# VLT_1_0.net
KiCad netlist of a schematic drawn in EAGLE
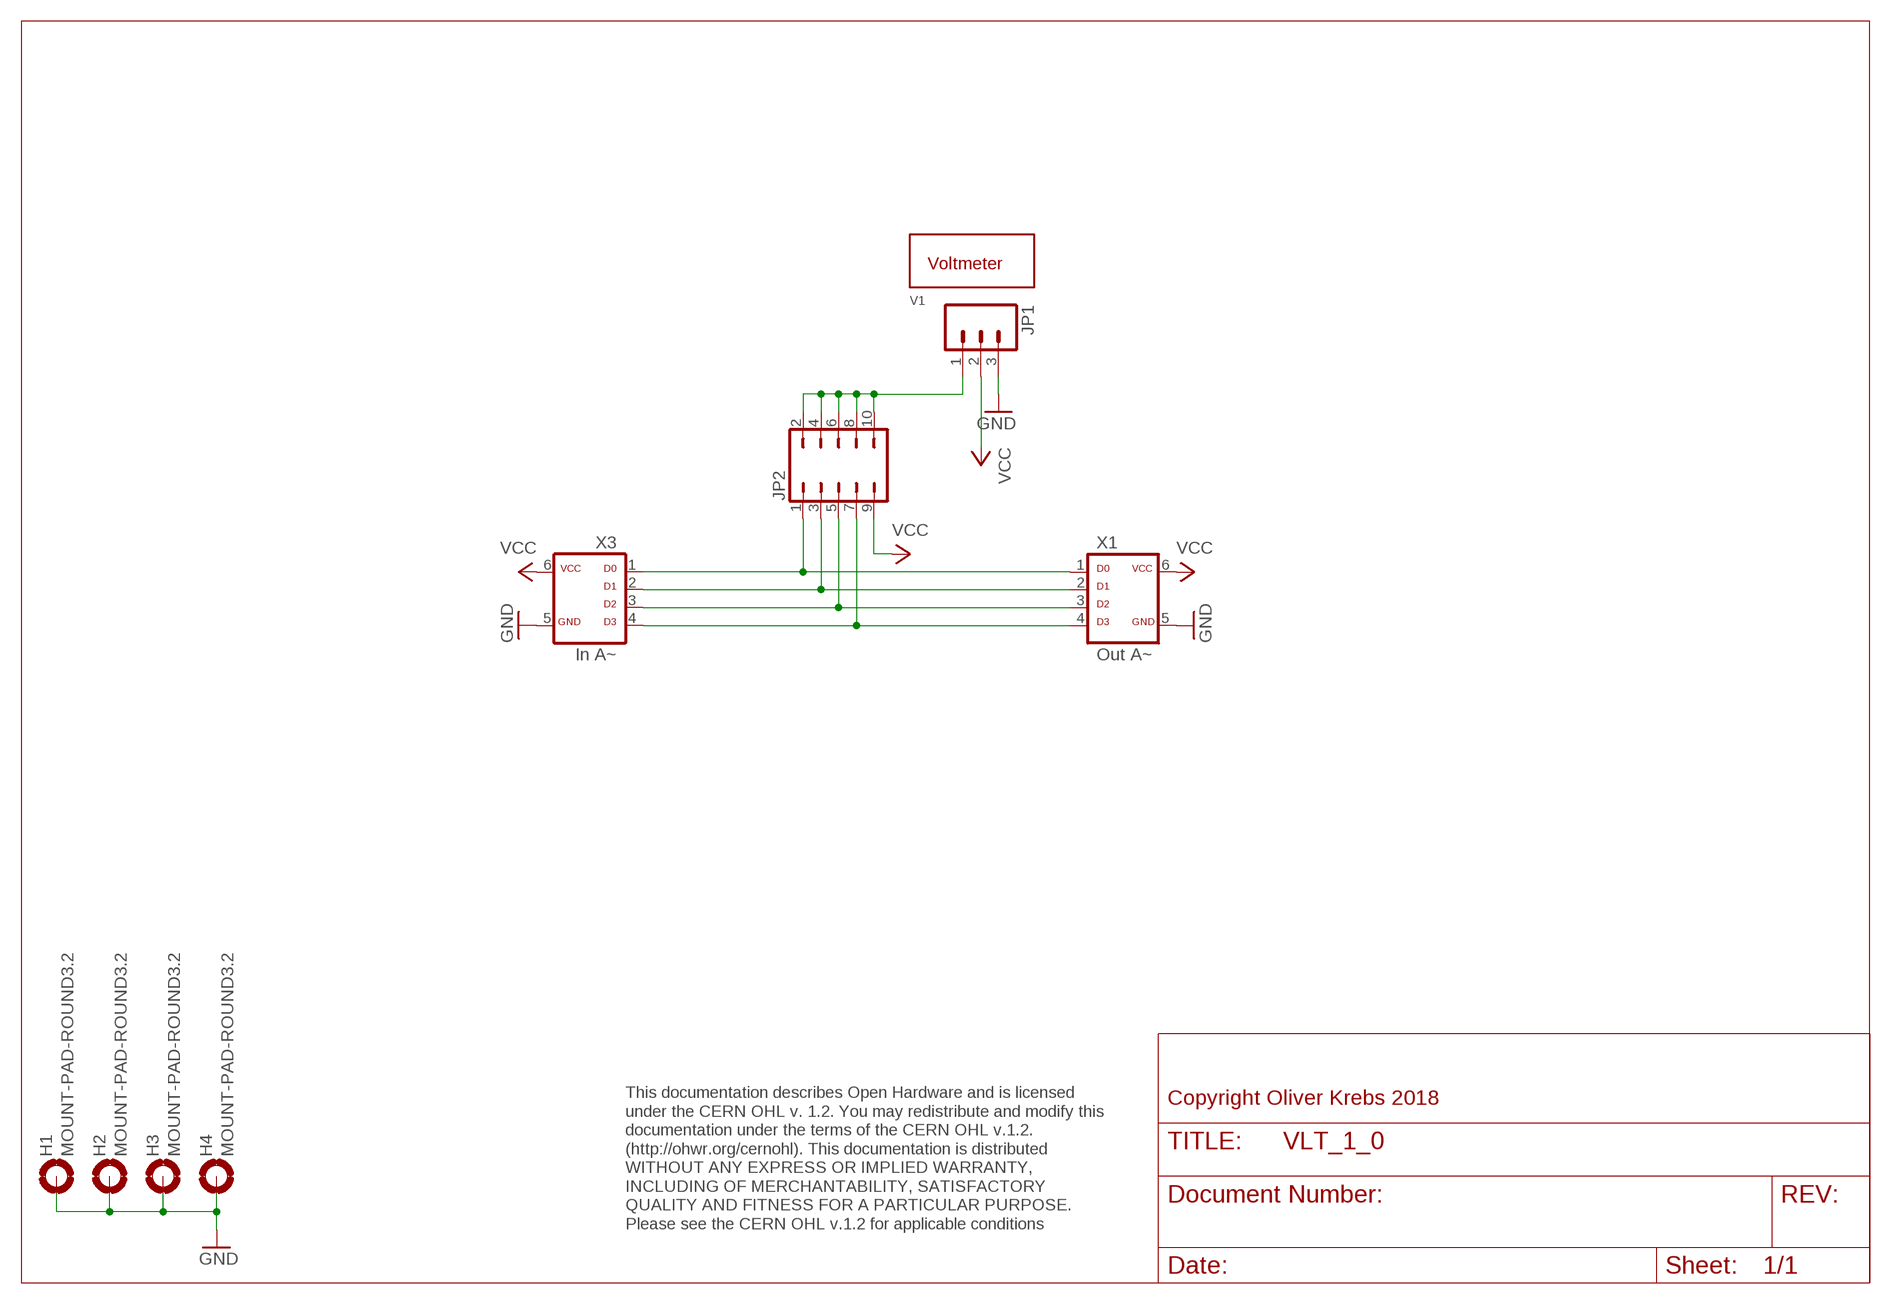
[diagram p0: schematic, sheet 1]

(export (version "E")
  (design (tool "Eeschema 10.0.6"))
  (components
    (comp (ref "H1")
      (value "MOUNT-PAD-ROUND3.2")
      (footprint "eagle-import:3,2-PAD")
      (libsource (lib "eagle-import") (part "MOUNT-PAD-ROUND3.2"))
    )
    (comp (ref "H2")
      (value "MOUNT-PAD-ROUND3.2")
      (footprint "eagle-import:3,2-PAD")
      (libsource (lib "eagle-import") (part "MOUNT-PAD-ROUND3.2"))
    )
    (comp (ref "H3")
      (value "MOUNT-PAD-ROUND3.2")
      (footprint "eagle-import:3,2-PAD")
      (libsource (lib "eagle-import") (part "MOUNT-PAD-ROUND3.2"))
    )
    (comp (ref "H4")
      (value "MOUNT-PAD-ROUND3.2")
      (footprint "eagle-import:3,2-PAD")
      (libsource (lib "eagle-import") (part "MOUNT-PAD-ROUND3.2"))
    )
    (comp (ref "JP1")
      (value "M03PTH")
      (footprint "eagle-import:1X03")
      (libsource (lib "eagle-import") (part "M03PTH"))
    )
    (comp (ref "JP2")
      (value "JP5Q")
      (footprint "eagle-import:JP5Q")
      (libsource (lib "eagle-import") (part "JP5Q"))
    )
    (comp (ref "V1")
      (value "VOLTMETER-28")
      (footprint "eagle-import:VOLTMETER-28")
      (libsource (lib "eagle-import") (part "VOLTMETER-28"))
    )
    (comp (ref "X1")
      (value "Out A~")
      (footprint "eagle-import:ML-6")
      (libsource (lib "eagle-import") (part "ML6D"))
    )
    (comp (ref "X3")
      (value "In A~")
      (footprint "eagle-import:ML-6")
      (libsource (lib "eagle-import") (part "ML6D"))
    )
  )
  (nets
    (net (code "1") (name "GND") (class "Default")
      (node (ref "H1") (pin "B3,2") (pinfunction "MOUNT_B3,2") (pintype "passive"))
      (node (ref "H2") (pin "B3,2") (pinfunction "MOUNT_B3,2") (pintype "passive"))
      (node (ref "H3") (pin "B3,2") (pinfunction "MOUNT_B3,2") (pintype "passive"))
      (node (ref "H4") (pin "B3,2") (pinfunction "MOUNT_B3,2") (pintype "passive"))
      (node (ref "JP1") (pin "3") (pinfunction "3_3") (pintype "passive"))
      (node (ref "X1") (pin "5") (pinfunction "5_5") (pintype "passive"))
      (node (ref "X3") (pin "5") (pinfunction "5_5") (pintype "passive"))
    )
    (net (code "2") (name "Net-(JP1-Pad1)") (class "Default")
      (node (ref "JP1") (pin "1") (pinfunction "1_1") (pintype "passive"))
      (node (ref "JP2") (pin "10") (pinfunction "10_10") (pintype "passive"))
      (node (ref "JP2") (pin "2") (pinfunction "2_2") (pintype "passive"))
      (node (ref "JP2") (pin "4") (pinfunction "4_4") (pintype "passive"))
      (node (ref "JP2") (pin "6") (pinfunction "6_6") (pintype "passive"))
      (node (ref "JP2") (pin "8") (pinfunction "8_8") (pintype "passive"))
    )
    (net (code "3") (name "Net-(JP2-Pad1)") (class "Default")
      (node (ref "JP2") (pin "1") (pinfunction "1_1") (pintype "passive"))
      (node (ref "X1") (pin "1") (pinfunction "1_1") (pintype "passive"))
      (node (ref "X3") (pin "1") (pinfunction "1_1") (pintype "passive"))
    )
    (net (code "4") (name "Net-(JP2-Pad3)") (class "Default")
      (node (ref "JP2") (pin "3") (pinfunction "3_3") (pintype "passive"))
      (node (ref "X1") (pin "2") (pinfunction "2_2") (pintype "passive"))
      (node (ref "X3") (pin "2") (pinfunction "2_2") (pintype "passive"))
    )
    (net (code "5") (name "Net-(JP2-Pad5)") (class "Default")
      (node (ref "JP2") (pin "5") (pinfunction "5_5") (pintype "passive"))
      (node (ref "X1") (pin "3") (pinfunction "3_3") (pintype "passive"))
      (node (ref "X3") (pin "3") (pinfunction "3_3") (pintype "passive"))
    )
    (net (code "6") (name "Net-(JP2-Pad7)") (class "Default")
      (node (ref "JP2") (pin "7") (pinfunction "7_7") (pintype "passive"))
      (node (ref "X1") (pin "4") (pinfunction "4_4") (pintype "passive"))
      (node (ref "X3") (pin "4") (pinfunction "4_4") (pintype "passive"))
    )
    (net (code "7") (name "VCC") (class "Default")
      (node (ref "JP1") (pin "2") (pinfunction "2_2") (pintype "passive"))
      (node (ref "JP2") (pin "9") (pinfunction "9_9") (pintype "passive"))
      (node (ref "X1") (pin "6") (pinfunction "6_6") (pintype "passive"))
      (node (ref "X3") (pin "6") (pinfunction "6_6") (pintype "passive"))
    )
  )
)
